# 10_Misc.net
KiCad netlist of a schematic drawn in Altium Designer
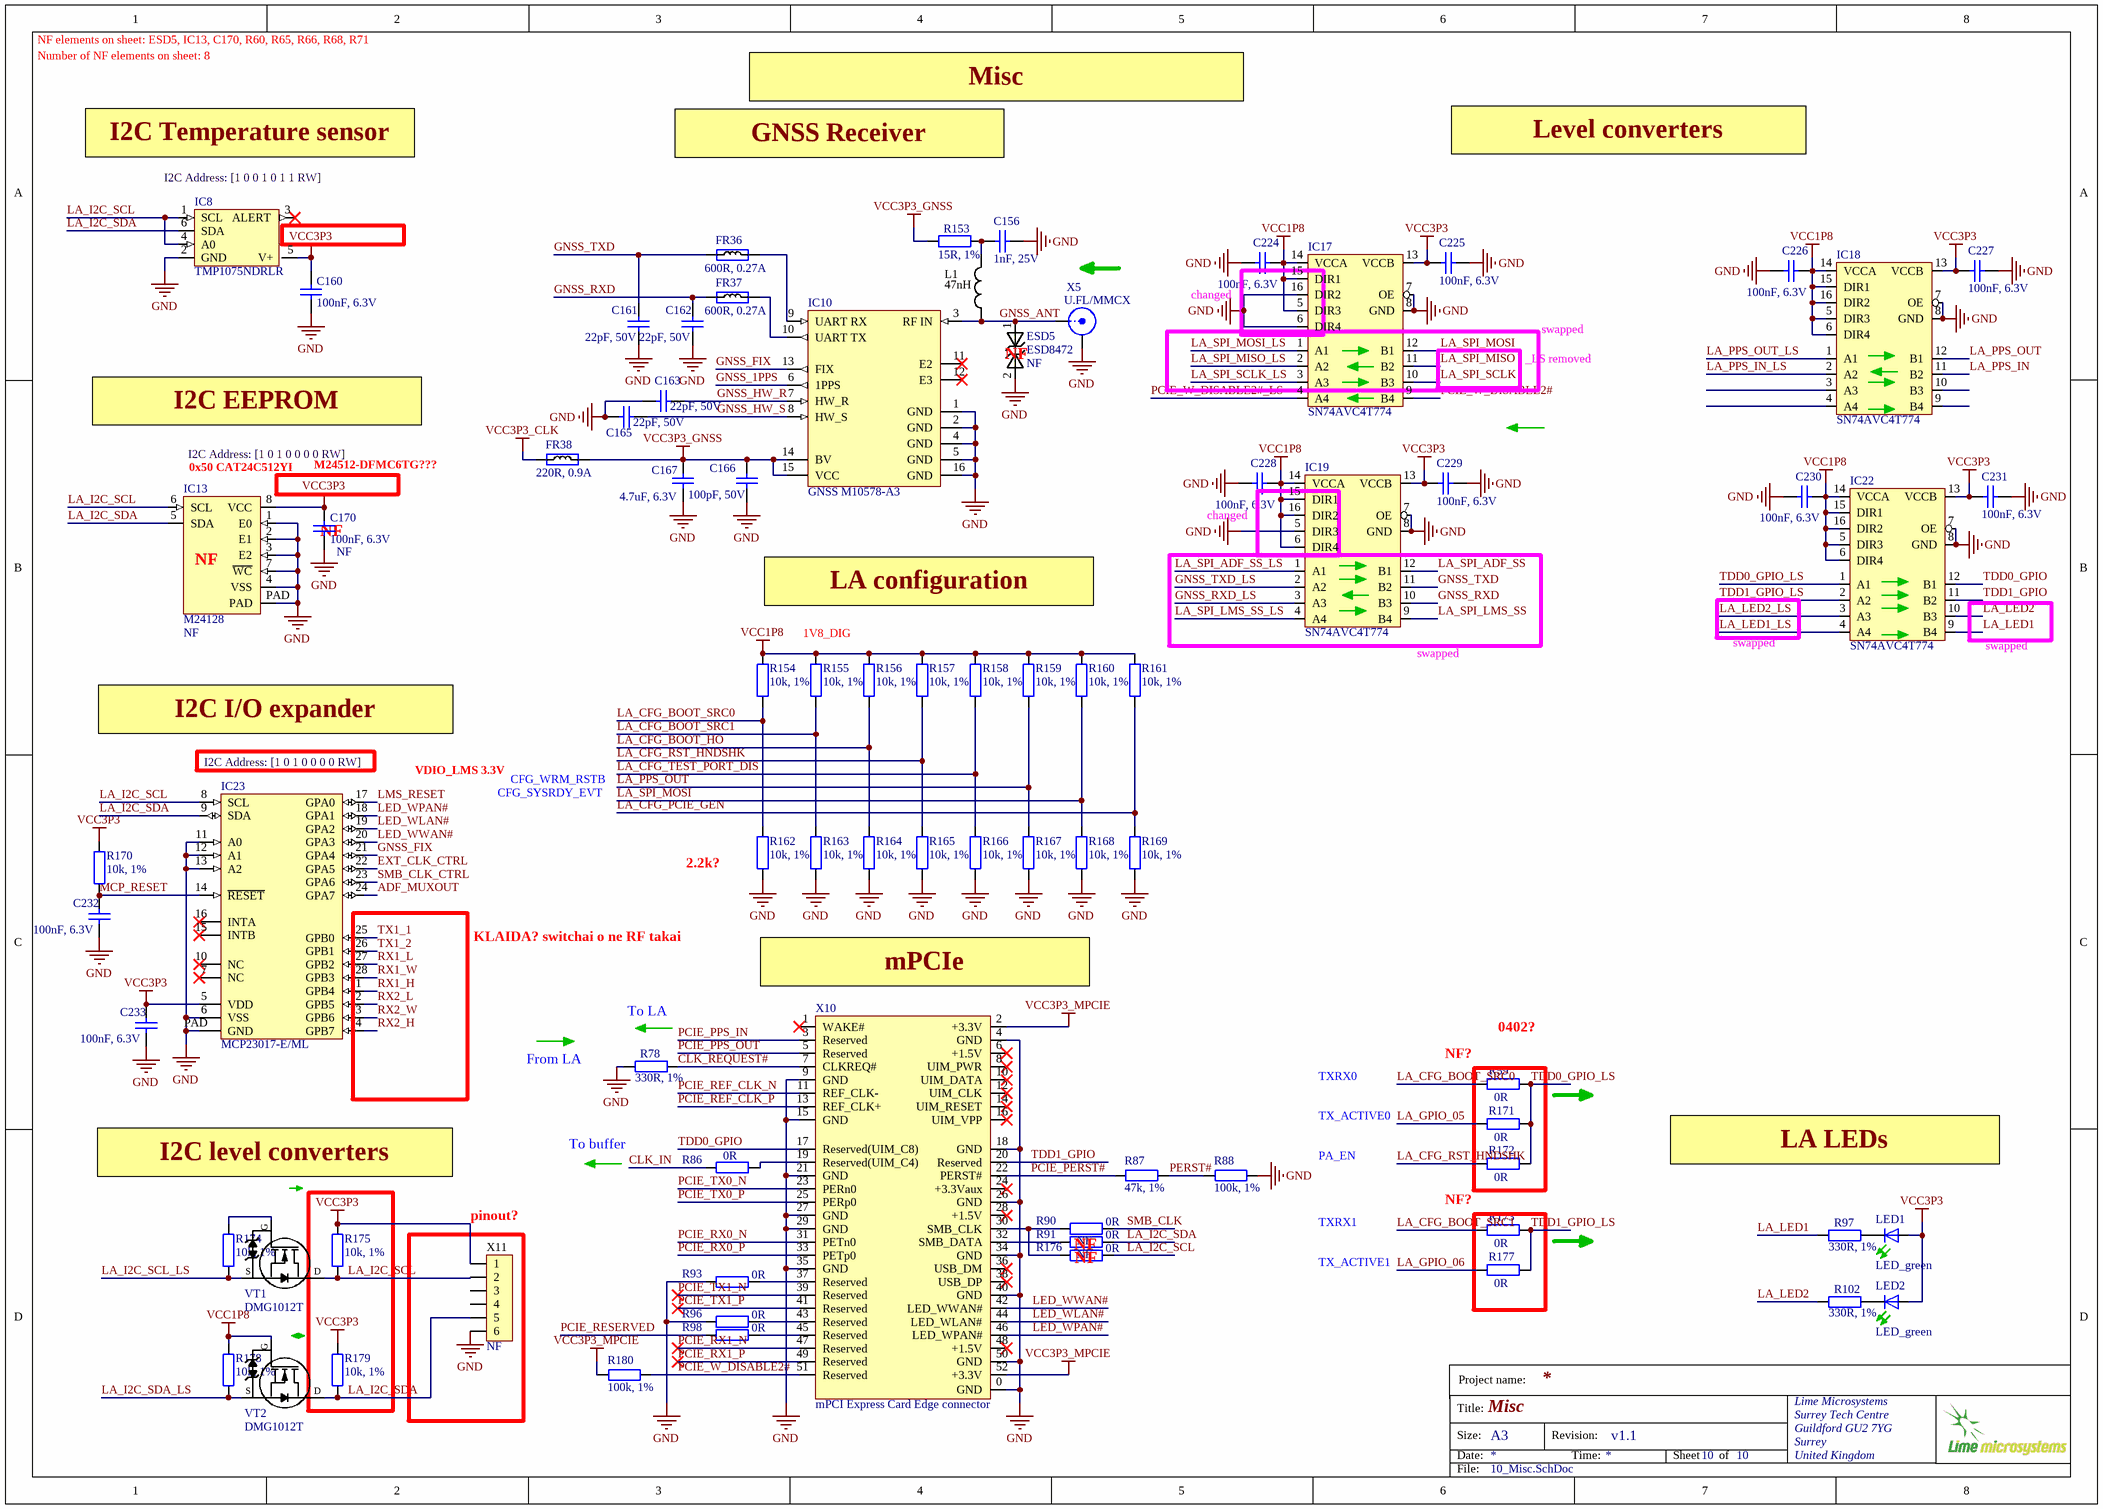
[diagram p0: 10_Misc.SchDoc]

(export (version "E")
  (design (tool "Eeschema 10.0.6"))
  (components
    (comp (ref "C156")
      (value "1nF, 25V")
      (footprint "CAP0201")
      (fields (field (name "TOLERANCE") "±10%") (field (name "MANUFACTURER") "TDK Corporation"))
      (libsource (lib "LimeMicroAltiumLib_schLib") (part "Cap_0402"))
    )
    (comp (ref "C160")
      (value "100nF, 6.3V")
      (footprint "CAP0201")
      (fields (field (name "MANUFACTURER") "Samsung") (field (name "TOLERANCE") "20%"))
      (libsource (lib "LimeMicroAltiumLib_schLib") (part "Cap_0402"))
    )
    (comp (ref "C161")
      (value "22pF, 50V")
      (footprint "CAP0201")
      (fields
        (field (name "MANUFACTURER") "Murata")
        (field (name "TOLERANCE") "5%")
        (field (name "VOLTAGE") "50V")
      )
      (libsource (lib "LimeMicroAltiumLib_schLib") (part "Cap_0402"))
    )
    (comp (ref "C162")
      (value "22pF, 50V")
      (footprint "CAP0201")
      (fields
        (field (name "MANUFACTURER") "Murata")
        (field (name "TOLERANCE") "5%")
        (field (name "VOLTAGE") "50V")
      )
      (libsource (lib "LimeMicroAltiumLib_schLib") (part "Cap_0402"))
    )
    (comp (ref "C163")
      (value "22pF, 50V")
      (footprint "CAP0201")
      (fields
        (field (name "MANUFACTURER") "Murata")
        (field (name "TOLERANCE") "5%")
        (field (name "VOLTAGE") "50V")
      )
      (libsource (lib "LimeMicroAltiumLib_schLib") (part "Cap_0402"))
    )
    (comp (ref "C165")
      (value "22pF, 50V")
      (footprint "CAP0201")
      (fields
        (field (name "MANUFACTURER") "Murata")
        (field (name "TOLERANCE") "5%")
        (field (name "VOLTAGE") "50V")
      )
      (libsource (lib "LimeMicroAltiumLib_schLib") (part "Cap_0402"))
    )
    (comp (ref "C166")
      (value "100pF, 50V")
      (footprint "CAP0201")
      (fields
        (field (name "MANUFACTURER") "TDK")
        (field (name "TOLERANCE") "5%")
        (field (name "VOLTAGE") "50V")
      )
      (libsource (lib "LimeMicroAltiumLib_schLib") (part "Cap_0402"))
    )
    (comp (ref "C167")
      (value "4.7uF, 6.3V")
      (footprint "CAP0402")
      (fields
        (field (name "MANUFACTURER") "Murata Electronics North America")
        (field (name "TOLERANCE") "±20%")
      )
      (libsource (lib "LimeMicroAltiumLib_schLib") (part "Cap_0402"))
    )
    (comp (ref "C170")
      (value "100nF, 6.3V")
      (footprint "CAP0201")
      (fields
        (field (name "ASSEMBLY INFO") "NF")
        (field (name "MANUFACTURER") "Samsung")
        (field (name "TOLERANCE") "20%")
      )
      (libsource (lib "LimeMicroAltiumLib_schLib") (part "Cap_0402"))
    )
    (comp (ref "C224")
      (value "100nF, 6.3V")
      (footprint "CAP0201")
      (fields (field (name "MANUFACTURER") "Samsung") (field (name "TOLERANCE") "20%"))
      (libsource (lib "LimeMicroAltiumLib_schLib") (part "Cap_0402"))
    )
    (comp (ref "C225")
      (value "100nF, 6.3V")
      (footprint "CAP0201")
      (fields (field (name "MANUFACTURER") "Samsung") (field (name "TOLERANCE") "20%"))
      (libsource (lib "LimeMicroAltiumLib_schLib") (part "Cap_0402"))
    )
    (comp (ref "C226")
      (value "100nF, 6.3V")
      (footprint "CAP0201")
      (fields (field (name "MANUFACTURER") "Samsung") (field (name "TOLERANCE") "20%"))
      (libsource (lib "LimeMicroAltiumLib_schLib") (part "Cap_0402"))
    )
    (comp (ref "C227")
      (value "100nF, 6.3V")
      (footprint "CAP0201")
      (fields (field (name "MANUFACTURER") "Samsung") (field (name "TOLERANCE") "20%"))
      (libsource (lib "LimeMicroAltiumLib_schLib") (part "Cap_0402"))
    )
    (comp (ref "C228")
      (value "100nF, 6.3V")
      (footprint "CAP0201")
      (fields (field (name "MANUFACTURER") "Samsung") (field (name "TOLERANCE") "20%"))
      (libsource (lib "LimeMicroAltiumLib_schLib") (part "Cap_0402"))
    )
    (comp (ref "C229")
      (value "100nF, 6.3V")
      (footprint "CAP0201")
      (fields (field (name "MANUFACTURER") "Samsung") (field (name "TOLERANCE") "20%"))
      (libsource (lib "LimeMicroAltiumLib_schLib") (part "Cap_0402"))
    )
    (comp (ref "C230")
      (value "100nF, 6.3V")
      (footprint "CAP0201")
      (fields (field (name "MANUFACTURER") "Samsung") (field (name "TOLERANCE") "20%"))
      (libsource (lib "LimeMicroAltiumLib_schLib") (part "Cap_0402"))
    )
    (comp (ref "C231")
      (value "100nF, 6.3V")
      (footprint "CAP0201")
      (fields (field (name "MANUFACTURER") "Samsung") (field (name "TOLERANCE") "20%"))
      (libsource (lib "LimeMicroAltiumLib_schLib") (part "Cap_0402"))
    )
    (comp (ref "C232")
      (value "100nF, 6.3V")
      (footprint "CAP0201")
      (fields (field (name "MANUFACTURER") "Samsung") (field (name "TOLERANCE") "20%"))
      (libsource (lib "LimeMicroAltiumLib_schLib") (part "Cap_0402"))
    )
    (comp (ref "C233")
      (value "100nF, 6.3V")
      (footprint "CAP0201")
      (fields (field (name "MANUFACTURER") "Samsung") (field (name "TOLERANCE") "20%"))
      (libsource (lib "LimeMicroAltiumLib_schLib") (part "Cap_0402"))
    )
    (comp (ref "ESD5")
      (value "ESD8472")
      (footprint "ESD8472_X3DFN2")
      (fields (field (name "MANUFACTURER") "ON Semiconductor") (field (name "ASSEMBLY INFO") "NF"))
      (libsource (lib "LimeMicroAltiumLib_schLib") (part "ESD8472"))
    )
    (comp (ref "FR36")
      (value "600R, 0.27A")
      (footprint "RES0201")
      (fields (field (name "MANUFACTURER") "Taiyo Yuden"))
      (libsource (lib "LimeMicroAltiumLib_schLib") (part "Ferrite"))
    )
    (comp (ref "FR37")
      (value "600R, 0.27A")
      (footprint "RES0201")
      (fields (field (name "MANUFACTURER") "Taiyo Yuden"))
      (libsource (lib "LimeMicroAltiumLib_schLib") (part "Ferrite"))
    )
    (comp (ref "FR38")
      (value "220R, 0.9A")
      (footprint "RES0402")
      (fields (field (name "MANUFACTURER") "TDK Corporation"))
      (libsource (lib "LimeFPGAboard_schLib") (part "Ferrite"))
    )
    (comp (ref "IC8")
      (value "TMP1075NDRLR")
      (footprint "TMP1075NDRLR_temperature_sensor_SOT563")
      (fields (field (name "MANUFACTURER") "Texas Instruments"))
      (libsource (lib "LimeMicroAltiumLib_schLib_r04") (part "TMP1075NDRLR_temperature_sensor"))
    )
    (comp (ref "IC10")
      (value "GNSS M10578-A3")
      (footprint "M10578-A3_v2")
      (fields (field (name "MANUFACTURER") "Antenova"))
      (libsource (lib "LimeMicroAltiumLib_schLib_r04") (part "M10578-A3_GPS_GNSS"))
    )
    (comp (ref "IC13")
      (value "M24128")
      (footprint "M24128-DFMC6TG")
      (fields (field (name "MANUFACTURER") "STMicroelectronics") (field (name "ASSEMBLY INFO") "NF"))
      (libsource (lib "LimeMicroAltiumLib_schLib") (part "M24128-DFMC6TG"))
    )
    (comp (ref "IC17")
      (value "SN74AVC4T774")
      (footprint "SN74AVC4T774")
      (fields (field (name "MANUFACTURER") "Texas Instruments"))
      (libsource (lib "LimeMicroAltiumLib") (part "SN74AVC4T774"))
    )
    (comp (ref "IC18")
      (value "SN74AVC4T774")
      (footprint "SN74AVC4T774")
      (fields (field (name "MANUFACTURER") "Texas Instruments"))
      (libsource (lib "LimeMicroAltiumLib") (part "SN74AVC4T774"))
    )
    (comp (ref "IC19")
      (value "SN74AVC4T774")
      (footprint "SN74AVC4T774")
      (fields (field (name "MANUFACTURER") "Texas Instruments"))
      (libsource (lib "LimeMicroAltiumLib") (part "SN74AVC4T774"))
    )
    (comp (ref "IC22")
      (value "SN74AVC4T774")
      (footprint "SN74AVC4T774")
      (fields (field (name "MANUFACTURER") "Texas Instruments"))
      (libsource (lib "LimeMicroAltiumLib") (part "SN74AVC4T774"))
    )
    (comp (ref "IC23")
      (value "MCP23017-E/ML")
      (footprint "MCP23017-E/ML_QFN28")
      (fields (field (name "MANUFACTURER") "Microchip"))
      (libsource (lib "LimeMicroAltiumLib") (part "MCP23017-E/ML_I2C_expander"))
    )
    (comp (ref "L1")
      (value "47nH")
      (footprint "RES0402")
      (fields
        (field (name "MANUFACTURER") "COILCRAFT")
        (field (name "MANUFACTURER PART NUMBER") "0402HP-47NXJLU")
      )
      (libsource (lib "LimeMicroAltiumLib_schLib") (part "Inductor_0603"))
    )
    (comp (ref "LED1")
      (value "LED_green")
      (footprint "LED0201")
      (fields (field (name "MANUFACTURER") "Kingbright"))
      (libsource (lib "LimeFPGAboard_schLib") (part "LED_green"))
    )
    (comp (ref "LED2")
      (value "LED_green")
      (footprint "LED0201")
      (fields (field (name "MANUFACTURER") "Kingbright"))
      (libsource (lib "LimeFPGAboard_schLib") (part "LED_green"))
    )
    (comp (ref "R59")
      (value "0R")
      (footprint "RES0201")
      (fields (field (name "MANUFACTURER") "Yageo") (field (name "TOLERANCE") "5%"))
      (libsource (lib "LimeFPGAboard_schLib") (part "Res_0402"))
    )
    (comp (ref "R78")
      (value "330R, 1%")
      (footprint "RES0201")
      (fields (field (name "MANUFACTURER") "Vishay Dale") (field (name "TOLERANCE") "1%"))
      (libsource (lib "LimeFPGAboard_schLib") (part "Res_0402"))
    )
    (comp (ref "R86")
      (value "0R")
      (footprint "RES0201")
      (fields (field (name "MANUFACTURER") "Yageo") (field (name "TOLERANCE") "5%"))
      (libsource (lib "LimeFPGAboard_schLib") (part "Res_0402"))
    )
    (comp (ref "R87")
      (value "47k, 1%")
      (footprint "RES0201")
      (fields (field (name "MANUFACTURER") "Yageo") (field (name "TOLERANCE") "1%"))
      (libsource (lib "LimeFPGAboard_schLib") (part "Res_0402"))
    )
    (comp (ref "R88")
      (value "100k, 1%")
      (footprint "RES0201")
      (fields (field (name "MANUFACTURER") "Yageo") (field (name "TOLERANCE") "1%"))
      (libsource (lib "LimeMicroAltiumLib_schLib") (part "Res_0402"))
    )
    (comp (ref "R90")
      (value "0R")
      (footprint "RES0201")
      (fields (field (name "MANUFACTURER") "Yageo") (field (name "TOLERANCE") "5%"))
      (libsource (lib "LimeFPGAboard_schLib") (part "Res_0402"))
    )
    (comp (ref "R91")
      (value "0R")
      (footprint "RES0201")
      (fields
        (field (name "ASSEMBLY INFO") "NF")
        (field (name "MANUFACTURER") "Yageo")
        (field (name "TOLERANCE") "5%")
      )
      (libsource (lib "LimeFPGAboard_schLib") (part "Res_0402"))
    )
    (comp (ref "R93")
      (value "0R")
      (footprint "RES0201")
      (fields (field (name "MANUFACTURER") "Yageo") (field (name "TOLERANCE") "5%"))
      (libsource (lib "LimeFPGAboard_schLib") (part "Res_0402"))
    )
    (comp (ref "R96")
      (value "0R")
      (footprint "RES0201")
      (fields (field (name "MANUFACTURER") "Yageo") (field (name "TOLERANCE") "5%"))
      (libsource (lib "LimeFPGAboard_schLib") (part "Res_0402"))
    )
    (comp (ref "R97")
      (value "330R, 1%")
      (footprint "RES0201")
      (fields (field (name "MANUFACTURER") "Vishay Dale") (field (name "TOLERANCE") "1%"))
      (libsource (lib "LimeFPGAboard_schLib") (part "Res_0402"))
    )
    (comp (ref "R98")
      (value "0R")
      (footprint "RES0201")
      (fields (field (name "MANUFACTURER") "Yageo") (field (name "TOLERANCE") "5%"))
      (libsource (lib "LimeFPGAboard_schLib") (part "Res_0402"))
    )
    (comp (ref "R102")
      (value "330R, 1%")
      (footprint "RES0201")
      (fields (field (name "MANUFACTURER") "Vishay Dale") (field (name "TOLERANCE") "1%"))
      (libsource (lib "LimeFPGAboard_schLib") (part "Res_0402"))
    )
    (comp (ref "R153")
      (value "15R, 1%")
      (footprint "RES0201")
      (fields (field (name "MANUFACTURER") "Yageo") (field (name "TOLERANCE") "1%"))
      (libsource (lib "LimeFPGAboard_schLib") (part "Res_0402"))
    )
    (comp (ref "R154")
      (value "10k, 1%")
      (footprint "RES0201")
      (fields (field (name "MANUFACTURER") "Yageo") (field (name "TOLERANCE") "1%"))
      (libsource (lib "LimeFPGAboard_schLib") (part "Res_0402"))
    )
    (comp (ref "R155")
      (value "10k, 1%")
      (footprint "RES0201")
      (fields (field (name "MANUFACTURER") "Yageo") (field (name "TOLERANCE") "1%"))
      (libsource (lib "LimeFPGAboard_schLib") (part "Res_0402"))
    )
    (comp (ref "R156")
      (value "10k, 1%")
      (footprint "RES0201")
      (fields (field (name "MANUFACTURER") "Yageo") (field (name "TOLERANCE") "1%"))
      (libsource (lib "LimeFPGAboard_schLib") (part "Res_0402"))
    )
    (comp (ref "R157")
      (value "10k, 1%")
      (footprint "RES0201")
      (fields (field (name "MANUFACTURER") "Yageo") (field (name "TOLERANCE") "1%"))
      (libsource (lib "LimeFPGAboard_schLib") (part "Res_0402"))
    )
    (comp (ref "R158")
      (value "10k, 1%")
      (footprint "RES0201")
      (fields (field (name "MANUFACTURER") "Yageo") (field (name "TOLERANCE") "1%"))
      (libsource (lib "LimeFPGAboard_schLib") (part "Res_0402"))
    )
    (comp (ref "R159")
      (value "10k, 1%")
      (footprint "RES0201")
      (fields (field (name "MANUFACTURER") "Yageo") (field (name "TOLERANCE") "1%"))
      (libsource (lib "LimeFPGAboard_schLib") (part "Res_0402"))
    )
    (comp (ref "R160")
      (value "10k, 1%")
      (footprint "RES0201")
      (fields (field (name "MANUFACTURER") "Yageo") (field (name "TOLERANCE") "1%"))
      (libsource (lib "LimeFPGAboard_schLib") (part "Res_0402"))
    )
    (comp (ref "R161")
      (value "10k, 1%")
      (footprint "RES0201")
      (fields (field (name "MANUFACTURER") "Yageo") (field (name "TOLERANCE") "1%"))
      (libsource (lib "LimeFPGAboard_schLib") (part "Res_0402"))
    )
    (comp (ref "R162")
      (value "10k, 1%")
      (footprint "RES0201")
      (fields (field (name "MANUFACTURER") "Yageo") (field (name "TOLERANCE") "1%"))
      (libsource (lib "LimeFPGAboard_schLib") (part "Res_0402"))
    )
    (comp (ref "R163")
      (value "10k, 1%")
      (footprint "RES0201")
      (fields (field (name "MANUFACTURER") "Yageo") (field (name "TOLERANCE") "1%"))
      (libsource (lib "LimeFPGAboard_schLib") (part "Res_0402"))
    )
    (comp (ref "R164")
      (value "10k, 1%")
      (footprint "RES0201")
      (fields (field (name "MANUFACTURER") "Yageo") (field (name "TOLERANCE") "1%"))
      (libsource (lib "LimeFPGAboard_schLib") (part "Res_0402"))
    )
    (comp (ref "R165")
      (value "10k, 1%")
      (footprint "RES0201")
      (fields (field (name "MANUFACTURER") "Yageo") (field (name "TOLERANCE") "1%"))
      (libsource (lib "LimeFPGAboard_schLib") (part "Res_0402"))
    )
    (comp (ref "R166")
      (value "10k, 1%")
      (footprint "RES0201")
      (fields (field (name "MANUFACTURER") "Yageo") (field (name "TOLERANCE") "1%"))
      (libsource (lib "LimeFPGAboard_schLib") (part "Res_0402"))
    )
    (comp (ref "R167")
      (value "10k, 1%")
      (footprint "RES0201")
      (fields (field (name "MANUFACTURER") "Yageo") (field (name "TOLERANCE") "1%"))
      (libsource (lib "LimeFPGAboard_schLib") (part "Res_0402"))
    )
    (comp (ref "R168")
      (value "10k, 1%")
      (footprint "RES0201")
      (fields (field (name "MANUFACTURER") "Yageo") (field (name "TOLERANCE") "1%"))
      (libsource (lib "LimeFPGAboard_schLib") (part "Res_0402"))
    )
    (comp (ref "R169")
      (value "10k, 1%")
      (footprint "RES0201")
      (fields (field (name "MANUFACTURER") "Yageo") (field (name "TOLERANCE") "1%"))
      (libsource (lib "LimeFPGAboard_schLib") (part "Res_0402"))
    )
    (comp (ref "R170")
      (value "10k, 1%")
      (footprint "RES0201")
      (fields (field (name "MANUFACTURER") "Yageo") (field (name "TOLERANCE") "1%"))
      (libsource (lib "LimeFPGAboard_schLib") (part "Res_0402"))
    )
    (comp (ref "R171")
      (value "0R")
      (footprint "RES0201")
      (fields (field (name "MANUFACTURER") "Yageo") (field (name "TOLERANCE") "5%"))
      (libsource (lib "LimeFPGAboard_schLib") (part "Res_0402"))
    )
    (comp (ref "R172")
      (value "0R")
      (footprint "RES0201")
      (fields (field (name "MANUFACTURER") "Yageo") (field (name "TOLERANCE") "5%"))
      (libsource (lib "LimeFPGAboard_schLib") (part "Res_0402"))
    )
    (comp (ref "R173")
      (value "0R")
      (footprint "RES0201")
      (fields (field (name "MANUFACTURER") "Yageo") (field (name "TOLERANCE") "5%"))
      (libsource (lib "LimeFPGAboard_schLib") (part "Res_0402"))
    )
    (comp (ref "R174")
      (value "10k, 1%")
      (footprint "RES0201")
      (fields (field (name "MANUFACTURER") "Yageo") (field (name "TOLERANCE") "1%"))
      (libsource (lib "LimeFPGAboard_schLib") (part "Res_0402"))
    )
    (comp (ref "R175")
      (value "10k, 1%")
      (footprint "RES0201")
      (fields (field (name "MANUFACTURER") "Yageo") (field (name "TOLERANCE") "1%"))
      (libsource (lib "LimeFPGAboard_schLib") (part "Res_0402"))
    )
    (comp (ref "R176")
      (value "0R")
      (footprint "RES0201")
      (fields
        (field (name "ASSEMBLY INFO") "NF")
        (field (name "MANUFACTURER") "Yageo")
        (field (name "TOLERANCE") "5%")
      )
      (libsource (lib "LimeFPGAboard_schLib") (part "Res_0402"))
    )
    (comp (ref "R177")
      (value "0R")
      (footprint "RES0201")
      (fields (field (name "MANUFACTURER") "Yageo") (field (name "TOLERANCE") "5%"))
      (libsource (lib "LimeFPGAboard_schLib") (part "Res_0402"))
    )
    (comp (ref "R178")
      (value "10k, 1%")
      (footprint "RES0201")
      (fields (field (name "MANUFACTURER") "Yageo") (field (name "TOLERANCE") "1%"))
      (libsource (lib "LimeFPGAboard_schLib") (part "Res_0402"))
    )
    (comp (ref "R179")
      (value "10k, 1%")
      (footprint "RES0201")
      (fields (field (name "MANUFACTURER") "Yageo") (field (name "TOLERANCE") "1%"))
      (libsource (lib "LimeFPGAboard_schLib") (part "Res_0402"))
    )
    (comp (ref "R180")
      (value "100k, 1%")
      (footprint "RES0201")
      (fields (field (name "MANUFACTURER") "Yageo") (field (name "TOLERANCE") "1%"))
      (libsource (lib "LimeMicroAltiumLib_schLib") (part "Res_0402"))
    )
    (comp (ref "VT1")
      (value "DMG1012T")
      (footprint "SOT523")
      (fields (field (name "MANUFACTURER") "Diodes Incorporated"))
      (libsource (lib "LimeMicroAltiumLib_schLib_r01") (part "DMG1012T"))
    )
    (comp (ref "VT2")
      (value "DMG1012T")
      (footprint "SOT523")
      (fields (field (name "MANUFACTURER") "Diodes Incorporated"))
      (libsource (lib "LimeMicroAltiumLib_schLib_r01") (part "DMG1012T"))
    )
    (comp (ref "X5")
      (value "U.FL/MMCX")
      (footprint "MMCX_UFL_conn_u_v2")
      (description "CONN UMC RCPT STR 50 OHM SMD")
      (fields (field (name "MANUFACTURER") "Molex, LLC"))
      (libsource (lib "LimeMicroAltiumLib_schLib") (part "RF_IF_connector"))
    )
    (comp (ref "X10")
      (value "mPCI Express Card Edge connector")
      (footprint "PCIe_MiniCard")
      (description "PCIe MiniCard full or half size")
      (libsource (lib "LimeMicroAltiumLib_schLib_r04") (part "PCIe_MiniCard_fingers"))
    )
    (comp (ref "X11")
      (value "Molex 0788641001")
      (footprint "Molex_0788641001_spring_contacts")
      (description "Header, 6-pin")
      (fields (field (name "MANUFACTURER") "Molex") (field (name "ASSEMBLY INFO") "NF"))
      (libsource (lib "LimeMicroAltiumLib_schLib_r04") (part "Molex_0788641001_spring_contacts"))
    )
  )
  (nets
    (net (code "1") (name "/ADF_MUXOUT") (class "Default")
      (node (ref "IC23") (pin "24") (pinfunction "GPA7_24") (pintype "bidirectional"))
    )
    (net (code "2") (name "/CLK_IN") (class "Default")
      (node (ref "R86") (pin "1") (pinfunction "1_1") (pintype "passive"))
    )
    (net (code "3") (name "/CLK_REQUEST#") (class "Default")
      (node (ref "R78") (pin "1") (pinfunction "1_1") (pintype "passive"))
      (node (ref "X10") (pin "7") (pinfunction "CLKREQ#_7") (pintype "passive"))
    )
    (net (code "4") (name "/EXT_CLK_CTRL") (class "Default")
      (node (ref "IC23") (pin "22") (pinfunction "GPA5_22") (pintype "bidirectional"))
    )
    (net (code "5") (name "/GNSS_1PPS") (class "Default")
      (node (ref "IC10") (pin "6") (pinfunction "1PPS_6") (pintype "output"))
    )
    (net (code "6") (name "/GNSS_ANT") (class "Default")
      (node (ref "ESD5") (pin "1") (pinfunction "1_1") (pintype "passive"))
      (node (ref "IC10") (pin "3") (pinfunction "RF_IN_3") (pintype "input"))
      (node (ref "L1") (pin "1") (pinfunction "1_1") (pintype "passive"))
      (node (ref "X5") (pin "1") (pinfunction "X_1") (pintype "passive"))
    )
    (net (code "7") (name "/GNSS_FIX") (class "Default")
      (node (ref "IC10") (pin "13") (pinfunction "FIX_13") (pintype "output"))
      (node (ref "IC23") (pin "21") (pinfunction "GPA4_21") (pintype "bidirectional"))
    )
    (net (code "8") (name "/GNSS_HW_R") (class "Default")
      (node (ref "C163") (pin "1") (pinfunction "1_1") (pintype "passive"))
      (node (ref "IC10") (pin "7") (pinfunction "HW_R_7") (pintype "input"))
    )
    (net (code "9") (name "/GNSS_HW_S") (class "Default")
      (node (ref "C165") (pin "1") (pinfunction "1_1") (pintype "passive"))
      (node (ref "IC10") (pin "8") (pinfunction "HW_S_8") (pintype "input"))
    )
    (net (code "10") (name "/GNSS_RXD") (class "Default")
      (node (ref "C162") (pin "1") (pinfunction "1_1") (pintype "passive"))
      (node (ref "FR37") (pin "1") (pinfunction "1_1") (pintype "passive"))
      (node (ref "IC19") (pin "10") (pinfunction "B3_10") (pintype "passive"))
    )
    (net (code "11") (name "/GNSS_RXD_LS") (class "Default")
      (node (ref "IC19") (pin "3") (pinfunction "A3_3") (pintype "passive"))
    )
    (net (code "12") (name "/GNSS_TXD") (class "Default")
      (node (ref "C161") (pin "1") (pinfunction "1_1") (pintype "passive"))
      (node (ref "FR36") (pin "1") (pinfunction "1_1") (pintype "passive"))
      (node (ref "IC19") (pin "11") (pinfunction "B2_11") (pintype "passive"))
    )
    (net (code "13") (name "/GNSS_TXD_LS") (class "Default")
      (node (ref "IC19") (pin "2") (pinfunction "A2_2") (pintype "passive"))
    )
    (net (code "14") (name "/LA_CFG_BOOT_HO") (class "Default")
      (node (ref "R156") (pin "2") (pinfunction "2_2") (pintype "passive"))
      (node (ref "R164") (pin "1") (pinfunction "1_1") (pintype "passive"))
    )
    (net (code "15") (name "/LA_CFG_BOOT_SRC0") (class "Default")
      (node (ref "R154") (pin "2") (pinfunction "2_2") (pintype "passive"))
      (node (ref "R162") (pin "1") (pinfunction "1_1") (pintype "passive"))
      (node (ref "R59") (pin "1") (pinfunction "1_1") (pintype "passive"))
    )
    (net (code "16") (name "/LA_CFG_BOOT_SRC1") (class "Default")
      (node (ref "R155") (pin "2") (pinfunction "2_2") (pintype "passive"))
      (node (ref "R163") (pin "1") (pinfunction "1_1") (pintype "passive"))
      (node (ref "R173") (pin "1") (pinfunction "1_1") (pintype "passive"))
    )
    (net (code "17") (name "/LA_CFG_PCIE_GEN") (class "Default")
      (node (ref "R161") (pin "2") (pinfunction "2_2") (pintype "passive"))
      (node (ref "R169") (pin "1") (pinfunction "1_1") (pintype "passive"))
    )
    (net (code "18") (name "/LA_CFG_RST_HNDSHK") (class "Default")
      (node (ref "R157") (pin "2") (pinfunction "2_2") (pintype "passive"))
      (node (ref "R165") (pin "1") (pinfunction "1_1") (pintype "passive"))
      (node (ref "R172") (pin "1") (pinfunction "1_1") (pintype "passive"))
    )
    (net (code "19") (name "/LA_CFG_TEST_PORT_DIS") (class "Default")
      (node (ref "R158") (pin "2") (pinfunction "2_2") (pintype "passive"))
      (node (ref "R166") (pin "1") (pinfunction "1_1") (pintype "passive"))
    )
    (net (code "20") (name "/LA_GPIO_05") (class "Default")
      (node (ref "R171") (pin "1") (pinfunction "1_1") (pintype "passive"))
    )
    (net (code "21") (name "/LA_GPIO_06") (class "Default")
      (node (ref "R177") (pin "1") (pinfunction "1_1") (pintype "passive"))
    )
    (net (code "22") (name "/LA_I2C_SCL") (class "Default")
      (node (ref "IC13") (pin "6") (pinfunction "SCL_6") (pintype "input"))
      (node (ref "IC23") (pin "8") (pinfunction "SCL_8") (pintype "input"))
      (node (ref "IC8") (pin "1") (pinfunction "SCL_1") (pintype "input"))
      (node (ref "IC8") (pin "4") (pinfunction "A0_4") (pintype "input"))
      (node (ref "R175") (pin "2") (pinfunction "2_2") (pintype "passive"))
      (node (ref "R176") (pin "2") (pinfunction "2_2") (pintype "passive"))
      (node (ref "VT1") (pin "D") (pinfunction "D_D") (pintype "passive"))
      (node (ref "X11") (pin "2") (pinfunction "2_2") (pintype "passive"))
    )
    (net (code "23") (name "/LA_I2C_SCL_LS") (class "Default")
      (node (ref "R174") (pin "2") (pinfunction "2_2") (pintype "passive"))
      (node (ref "VT1") (pin "S") (pinfunction "S_S") (pintype "passive"))
    )
    (net (code "24") (name "/LA_I2C_SDA") (class "Default")
      (node (ref "IC13") (pin "5") (pinfunction "SDA_5") (pintype "bidirectional"))
      (node (ref "IC23") (pin "9") (pinfunction "SDA_9") (pintype "bidirectional"))
      (node (ref "IC8") (pin "6") (pinfunction "SDA_6") (pintype "bidirectional"))
      (node (ref "R179") (pin "2") (pinfunction "2_2") (pintype "passive"))
      (node (ref "R91") (pin "2") (pinfunction "2_2") (pintype "passive"))
      (node (ref "VT2") (pin "D") (pinfunction "D_D") (pintype "passive"))
      (node (ref "X11") (pin "5") (pinfunction "5_5") (pintype "passive"))
    )
    (net (code "25") (name "/LA_I2C_SDA_LS") (class "Default")
      (node (ref "R178") (pin "2") (pinfunction "2_2") (pintype "passive"))
      (node (ref "VT2") (pin "S") (pinfunction "S_S") (pintype "passive"))
    )
    (net (code "26") (name "/LA_LED1") (class "Default")
      (node (ref "IC22") (pin "9") (pinfunction "B4_9") (pintype "passive"))
      (node (ref "R97") (pin "2") (pinfunction "2_2") (pintype "passive"))
    )
    (net (code "27") (name "/LA_LED1_LS") (class "Default")
      (node (ref "IC22") (pin "4") (pinfunction "A4_4") (pintype "passive"))
    )
    (net (code "28") (name "/LA_LED2") (class "Default")
      (node (ref "IC22") (pin "10") (pinfunction "B3_10") (pintype "passive"))
      (node (ref "R102") (pin "2") (pinfunction "2_2") (pintype "passive"))
    )
    (net (code "29") (name "/LA_LED2_LS") (class "Default")
      (node (ref "IC22") (pin "3") (pinfunction "A3_3") (pintype "passive"))
    )
    (net (code "30") (name "/LA_PPS_IN") (class "Default")
      (node (ref "IC18") (pin "11") (pinfunction "B2_11") (pintype "passive"))
    )
    (net (code "31") (name "/LA_PPS_IN_LS") (class "Default")
      (node (ref "IC18") (pin "2") (pinfunction "A2_2") (pintype "passive"))
    )
    (net (code "32") (name "/LA_PPS_OUT") (class "Default")
      (node (ref "IC18") (pin "12") (pinfunction "B1_12") (pintype "passive"))
      (node (ref "R159") (pin "2") (pinfunction "2_2") (pintype "passive"))
      (node (ref "R167") (pin "1") (pinfunction "1_1") (pintype "passive"))
    )
    (net (code "33") (name "/LA_PPS_OUT_LS") (class "Default")
      (node (ref "IC18") (pin "1") (pinfunction "A1_1") (pintype "passive"))
    )
    (net (code "34") (name "/LA_SPI_ADF_SS") (class "Default")
      (node (ref "IC19") (pin "12") (pinfunction "B1_12") (pintype "passive"))
    )
    (net (code "35") (name "/LA_SPI_ADF_SS_LS") (class "Default")
      (node (ref "IC19") (pin "1") (pinfunction "A1_1") (pintype "passive"))
    )
    (net (code "36") (name "/LA_SPI_LMS_SS") (class "Default")
      (node (ref "IC19") (pin "9") (pinfunction "B4_9") (pintype "passive"))
    )
    (net (code "37") (name "/LA_SPI_LMS_SS_LS") (class "Default")
      (node (ref "IC19") (pin "4") (pinfunction "A4_4") (pintype "passive"))
    )
    (net (code "38") (name "/LA_SPI_MISO") (class "Default")
      (node (ref "IC17") (pin "11") (pinfunction "B2_11") (pintype "passive"))
    )
    (net (code "39") (name "/LA_SPI_MISO_LS") (class "Default")
      (node (ref "IC17") (pin "2") (pinfunction "A2_2") (pintype "passive"))
    )
    (net (code "40") (name "/LA_SPI_MOSI") (class "Default")
      (node (ref "IC17") (pin "12") (pinfunction "B1_12") (pintype "passive"))
      (node (ref "R160") (pin "2") (pinfunction "2_2") (pintype "passive"))
      (node (ref "R168") (pin "1") (pinfunction "1_1") (pintype "passive"))
    )
    (net (code "41") (name "/LA_SPI_MOSI_LS") (class "Default")
      (node (ref "IC17") (pin "1") (pinfunction "A1_1") (pintype "passive"))
    )
    (net (code "42") (name "/LA_SPI_SCLK") (class "Default")
      (node (ref "IC17") (pin "10") (pinfunction "B3_10") (pintype "passive"))
    )
    (net (code "43") (name "/LA_SPI_SCLK_LS") (class "Default")
      (node (ref "IC17") (pin "3") (pinfunction "A3_3") (pintype "passive"))
    )
    (net (code "44") (name "/LED_WLAN#") (class "Default")
      (node (ref "IC23") (pin "19") (pinfunction "GPA2_19") (pintype "bidirectional"))
      (node (ref "X10") (pin "44") (pinfunction "LED_WLAN#_44") (pintype "passive"))
    )
    (net (code "45") (name "/LED_WPAN#") (class "Default")
      (node (ref "IC23") (pin "18") (pinfunction "GPA1_18") (pintype "bidirectional"))
      (node (ref "X10") (pin "46") (pinfunction "LED_WPAN#_46") (pintype "passive"))
    )
    (net (code "46") (name "/LED_WWAN#") (class "Default")
      (node (ref "IC23") (pin "20") (pinfunction "GPA3_20") (pintype "bidirectional"))
      (node (ref "X10") (pin "42") (pinfunction "LED_WWAN#_42") (pintype "passive"))
    )
    (net (code "47") (name "/LMS_RESET") (class "Default")
      (node (ref "IC23") (pin "17") (pinfunction "GPA0_17") (pintype "bidirectional"))
    )
    (net (code "48") (name "/MCP_RESET") (class "Default")
      (node (ref "C232") (pin "1") (pinfunction "1_1") (pintype "passive"))
      (node (ref "IC23") (pin "14") (pinfunction "~{RESET}_14") (pintype "input"))
      (node (ref "R170") (pin "2") (pinfunction "2_2") (pintype "passive"))
    )
    (net (code "49") (name "/PCIE_PERST#") (class "Default")
      (node (ref "R87") (pin "1") (pinfunction "1_1") (pintype "passive"))
      (node (ref "X10") (pin "22") (pinfunction "PERST#_22") (pintype "passive"))
    )
    (net (code "50") (name "/PCIE_PPS_IN") (class "Default")
      (node (ref "X10") (pin "3") (pinfunction "Reserved_3") (pintype "passive"))
    )
    (net (code "51") (name "/PCIE_PPS_OUT") (class "Default")
      (node (ref "X10") (pin "5") (pinfunction "Reserved_5") (pintype "passive"))
    )
    (net (code "52") (name "/PCIE_REF_CLK_N") (class "Default")
      (node (ref "X10") (pin "11") (pinfunction "REF_CLK-_11") (pintype "passive"))
    )
    (net (code "53") (name "/PCIE_REF_CLK_P") (class "Default")
      (node (ref "X10") (pin "13") (pinfunction "REF_CLK+_13") (pintype "passive"))
    )
    (net (code "54") (name "/PCIE_RESERVED") (class "Default")
      (node (ref "R98") (pin "1") (pinfunction "1_1") (pintype "passive"))
    )
    (net (code "55") (name "/PCIE_RX0_N") (class "Default")
      (node (ref "X10") (pin "31") (pinfunction "PETn0_31") (pintype "passive"))
    )
    (net (code "56") (name "/PCIE_RX0_P") (class "Default")
      (node (ref "X10") (pin "33") (pinfunction "PETp0_33") (pintype "passive"))
    )
    (net (code "57") (name "/PCIE_RX1_N") (class "Default")
      (node (ref "X10") (pin "47") (pinfunction "Reserved_47") (pintype "passive+no_connect"))
    )
    (net (code "58") (name "/PCIE_RX1_P") (class "Default")
      (node (ref "X10") (pin "49") (pinfunction "Reserved_49") (pintype "passive+no_connect"))
    )
    (net (code "59") (name "/PCIE_TX0_N") (class "Default")
      (node (ref "X10") (pin "23") (pinfunction "PERn0_23") (pintype "passive"))
    )
    (net (code "60") (name "/PCIE_TX0_P") (class "Default")
      (node (ref "X10") (pin "25") (pinfunction "PERp0_25") (pintype "passive"))
    )
    (net (code "61") (name "/PCIE_TX1_N") (class "Default")
      (node (ref "X10") (pin "39") (pinfunction "Reserved_39") (pintype "passive+no_connect"))
    )
    (net (code "62") (name "/PCIE_TX1_P") (class "Default")
      (node (ref "X10") (pin "41") (pinfunction "Reserved_41") (pintype "passive+no_connect"))
    )
    (net (code "63") (name "/PCIE_W_DISABLE2#") (class "Default")
      (node (ref "IC17") (pin "9") (pinfunction "B4_9") (pintype "passive"))
      (node (ref "R180") (pin "1") (pinfunction "1_1") (pintype "passive"))
      (node (ref "X10") (pin "51") (pinfunction "Reserved_51") (pintype "passive"))
    )
    (net (code "64") (name "/PCIE_W_DISABLE2#_LS") (class "Default")
      (node (ref "IC17") (pin "4") (pinfunction "A4_4") (pintype "passive"))
    )
    (net (code "65") (name "/PERST#") (class "Default")
      (node (ref "R87") (pin "2") (pinfunction "2_2") (pintype "passive"))
      (node (ref "R88") (pin "2") (pinfunction "2_2") (pintype "passive"))
    )
    (net (code "66") (name "/RX1_H") (class "Default")
      (node (ref "IC23") (pin "1") (pinfunction "GPB4_1") (pintype "bidirectional"))
    )
    (net (code "67") (name "/RX1_L") (class "Default")
      (node (ref "IC23") (pin "27") (pinfunction "GPB2_27") (pintype "bidirectional"))
    )
    (net (code "68") (name "/RX1_W") (class "Default")
      (node (ref "IC23") (pin "28") (pinfunction "GPB3_28") (pintype "bidirectional"))
    )
    (net (code "69") (name "/RX2_H") (class "Default")
      (node (ref "IC23") (pin "4") (pinfunction "GPB7_4") (pintype "bidirectional"))
    )
    (net (code "70") (name "/RX2_L") (class "Default")
      (node (ref "IC23") (pin "2") (pinfunction "GPB5_2") (pintype "bidirectional"))
    )
    (net (code "71") (name "/RX2_W") (class "Default")
      (node (ref "IC23") (pin "3") (pinfunction "GPB6_3") (pintype "bidirectional"))
    )
    (net (code "72") (name "/SMB_CLK") (class "Default")
      (node (ref "R90") (pin "2") (pinfunction "2_2") (pintype "passive"))
    )
    (net (code "73") (name "/SMB_CLK_CTRL") (class "Default")
      (node (ref "IC23") (pin "23") (pinfunction "GPA6_23") (pintype "bidirectional"))
    )
    (net (code "74") (name "/TDD0_GPIO") (class "Default")
      (node (ref "IC22") (pin "12") (pinfunction "B1_12") (pintype "passive"))
      (node (ref "X10") (pin "17") (pinfunction "Reserved(UIM_C8)_17") (pintype "passive"))
    )
    (net (code "75") (name "/TDD0_GPIO_LS") (class "Default")
      (node (ref "IC22") (pin "1") (pinfunction "A1_1") (pintype "passive"))
      (node (ref "R171") (pin "2") (pinfunction "2_2") (pintype "passive"))
      (node (ref "R172") (pin "2") (pinfunction "2_2") (pintype "passive"))
      (node (ref "R59") (pin "2") (pinfunction "2_2") (pintype "passive"))
    )
    (net (code "76") (name "/TDD1_GPIO") (class "Default")
      (node (ref "IC22") (pin "11") (pinfunction "B2_11") (pintype "passive"))
      (node (ref "X10") (pin "20") (pinfunction "Reserved_20") (pintype "passive"))
    )
    (net (code "77") (name "/TDD1_GPIO_LS") (class "Default")
      (node (ref "IC22") (pin "2") (pinfunction "A2_2") (pintype "passive"))
      (node (ref "R173") (pin "2") (pinfunction "2_2") (pintype "passive"))
      (node (ref "R177") (pin "2") (pinfunction "2_2") (pintype "passive"))
    )
    (net (code "78") (name "/TX1_1") (class "Default")
      (node (ref "IC23") (pin "25") (pinfunction "GPB0_25") (pintype "bidirectional"))
    )
    (net (code "79") (name "/TX1_2") (class "Default")
      (node (ref "IC23") (pin "26") (pinfunction "GPB1_26") (pintype "bidirectional"))
    )
    (net (code "80") (name "GND") (class "Default")
      (node (ref "C156") (pin "2") (pinfunction "2_2") (pintype "passive"))
      (node (ref "C160") (pin "2") (pinfunction "2_2") (pintype "passive"))
      (node (ref "C161") (pin "2") (pinfunction "2_2") (pintype "passive"))
      (node (ref "C162") (pin "2") (pinfunction "2_2") (pintype "passive"))
      (node (ref "C163") (pin "2") (pinfunction "2_2") (pintype "passive"))
      (node (ref "C165") (pin "2") (pinfunction "2_2") (pintype "passive"))
      (node (ref "C166") (pin "1") (pinfunction "1_1") (pintype "passive"))
      (node (ref "C167") (pin "1") (pinfunction "1_1") (pintype "passive"))
      (node (ref "C170") (pin "2") (pinfunction "2_2") (pintype "passive"))
      (node (ref "C224") (pin "1") (pinfunction "1_1") (pintype "passive"))
      (node (ref "C225") (pin "2") (pinfunction "2_2") (pintype "passive"))
      (node (ref "C226") (pin "1") (pinfunction "1_1") (pintype "passive"))
      (node (ref "C227") (pin "2") (pinfunction "2_2") (pintype "passive"))
      (node (ref "C228") (pin "1") (pinfunction "1_1") (pintype "passive"))
      (node (ref "C229") (pin "2") (pinfunction "2_2") (pintype "passive"))
      (node (ref "C230") (pin "1") (pinfunction "1_1") (pintype "passive"))
      (node (ref "C231") (pin "2") (pinfunction "2_2") (pintype "passive"))
      (node (ref "C232") (pin "2") (pinfunction "2_2") (pintype "passive"))
      (node (ref "C233") (pin "2") (pinfunction "2_2") (pintype "passive"))
      (node (ref "ESD5") (pin "2") (pinfunction "2_2") (pintype "passive"))
      (node (ref "IC10") (pin "1") (pinfunction "GND_1") (pintype "passive"))
      (node (ref "IC10") (pin "16") (pinfunction "GND_16") (pintype "passive"))
      (node (ref "IC10") (pin "2") (pinfunction "GND_2") (pintype "passive"))
      (node (ref "IC10") (pin "4") (pinfunction "GND_4") (pintype "passive"))
      (node (ref "IC10") (pin "5") (pinfunction "GND_5") (pintype "passive"))
      (node (ref "IC13") (pin "1") (pinfunction "E0_1") (pintype "input"))
      (node (ref "IC13") (pin "2") (pinfunction "E1_2") (pintype "input"))
      (node (ref "IC13") (pin "3") (pinfunction "E2_3") (pintype "input"))
      (node (ref "IC13") (pin "4") (pinfunction "VSS_4") (pintype "power_in"))
      (node (ref "IC13") (pin "7") (pinfunction "~{WC}_7") (pintype "input"))
      (node (ref "IC13") (pin "PAD") (pinfunction "PAD_PAD") (pintype "power_in"))
      (node (ref "IC17") (pin "16") (pinfunction "DIR2_16") (pintype "passive"))
      (node (ref "IC17") (pin "6") (pinfunction "DIR4_6") (pintype "passive"))
      (node (ref "IC17") (pin "7") (pinfunction "OE_7") (pintype "passive"))
      (node (ref "IC17") (pin "8") (pinfunction "GND_8") (pintype "passive"))
      (node (ref "IC18") (pin "7") (pinfunction "OE_7") (pintype "passive"))
      (node (ref "IC18") (pin "8") (pinfunction "GND_8") (pintype "passive"))
      (node (ref "IC19") (pin "5") (pinfunction "DIR3_5") (pintype "passive"))
      (node (ref "IC19") (pin "7") (pinfunction "OE_7") (pintype "passive"))
      (node (ref "IC19") (pin "8") (pinfunction "GND_8") (pintype "passive"))
      (node (ref "IC22") (pin "7") (pinfunction "OE_7") (pintype "passive"))
      (node (ref "IC22") (pin "8") (pinfunction "GND_8") (pintype "passive"))
      (node (ref "IC23") (pin "11") (pinfunction "A0_11") (pintype "input"))
      (node (ref "IC23") (pin "12") (pinfunction "A1_12") (pintype "input"))
      (node (ref "IC23") (pin "13") (pinfunction "A2_13") (pintype "input"))
      (node (ref "IC23") (pin "6") (pinfunction "VSS_6") (pintype "power_in"))
      (node (ref "IC23") (pin "PAD") (pinfunction "GND_PAD") (pintype "passive"))
      (node (ref "IC8") (pin "2") (pinfunction "GND_2") (pintype "passive"))
      (node (ref "R162") (pin "2") (pinfunction "2_2") (pintype "passive"))
      (node (ref "R163") (pin "2") (pinfunction "2_2") (pintype "passive"))
      (node (ref "R164") (pin "2") (pinfunction "2_2") (pintype "passive"))
      (node (ref "R165") (pin "2") (pinfunction "2_2") (pintype "passive"))
      (node (ref "R166") (pin "2") (pinfunction "2_2") (pintype "passive"))
      (node (ref "R167") (pin "2") (pinfunction "2_2") (pintype "passive"))
      (node (ref "R168") (pin "2") (pinfunction "2_2") (pintype "passive"))
      (node (ref "R169") (pin "2") (pinfunction "2_2") (pintype "passive"))
      (node (ref "R78") (pin "2") (pinfunction "2_2") (pintype "passive"))
      (node (ref "R88") (pin "1") (pinfunction "1_1") (pintype "passive"))
      (node (ref "R93") (pin "1") (pinfunction "1_1") (pintype "passive"))
      (node (ref "R96") (pin "1") (pinfunction "1_1") (pintype "passive"))
      (node (ref "X10") (pin "0") (pinfunction "GND_0") (pintype "passive"))
      (node (ref "X10") (pin "15") (pinfunction "GND_15") (pintype "passive"))
      (node (ref "X10") (pin "18") (pinfunction "GND_18") (pintype "passive"))
      (node (ref "X10") (pin "21") (pinfunction "GND_21") (pintype "passive"))
      (node (ref "X10") (pin "26") (pinfunction "GND_26") (pintype "passive"))
      (node (ref "X10") (pin "27") (pinfunction "GND_27") (pintype "passive"))
      (node (ref "X10") (pin "29") (pinfunction "GND_29") (pintype "passive"))
      (node (ref "X10") (pin "34") (pinfunction "GND_34") (pintype "passive"))
      (node (ref "X10") (pin "35") (pinfunction "GND_35") (pintype "passive"))
      (node (ref "X10") (pin "4") (pinfunction "GND_4") (pintype "passive"))
      (node (ref "X10") (pin "40") (pinfunction "GND_40") (pintype "passive"))
      (node (ref "X10") (pin "50") (pinfunction "GND_50") (pintype "passive"))
      (node (ref "X10") (pin "9") (pinfunction "GND_9") (pintype "passive"))
      (node (ref "X11") (pin "6") (pinfunction "6_6") (pintype "passive"))
      (node (ref "X5") (pin "2") (pinfunction "Y_2") (pintype "passive"))
    )
    (net (code "81") (name "Net-(C156-Pad1)") (class "Default")
      (node (ref "C156") (pin "1") (pinfunction "1_1") (pintype "passive"))
      (node (ref "L1") (pin "2") (pinfunction "2_2") (pintype "passive"))
      (node (ref "R153") (pin "1") (pinfunction "1_1") (pintype "passive"))
    )
    (net (code "82") (name "Net-(IC10-UART_RX)") (class "Default")
      (node (ref "FR36") (pin "2") (pinfunction "2_2") (pintype "passive"))
      (node (ref "IC10") (pin "9") (pinfunction "UART_RX_9") (pintype "input"))
    )
    (net (code "83") (name "Net-(IC10-UART_TX)") (class "Default")
      (node (ref "FR37") (pin "2") (pinfunction "2_2") (pintype "passive"))
      (node (ref "IC10") (pin "10") (pinfunction "UART_TX_10") (pintype "output"))
    )
    (net (code "84") (name "Net-(LED1-C)") (class "Default")
      (node (ref "LED1") (pin "K") (pinfunction "C_K") (pintype "power_in"))
      (node (ref "R97") (pin "1") (pinfunction "1_1") (pintype "passive"))
    )
    (net (code "85") (name "Net-(LED2-C)") (class "Default")
      (node (ref "LED2") (pin "K") (pinfunction "C_K") (pintype "power_in"))
      (node (ref "R102") (pin "1") (pinfunction "1_1") (pintype "passive"))
    )
    (net (code "86") (name "Net-(R93-Pad2)") (class "Default")
      (node (ref "R93") (pin "2") (pinfunction "2_2") (pintype "passive"))
      (node (ref "X10") (pin "37") (pinfunction "Reserved_37") (pintype "passive"))
    )
    (net (code "87") (name "Net-(R96-Pad2)") (class "Default")
      (node (ref "R96") (pin "2") (pinfunction "2_2") (pintype "passive"))
      (node (ref "X10") (pin "43") (pinfunction "Reserved_43") (pintype "passive"))
    )
    (net (code "88") (name "Net-(R98-Pad2)") (class "Default")
      (node (ref "R98") (pin "2") (pinfunction "2_2") (pintype "passive"))
      (node (ref "X10") (pin "45") (pinfunction "Reserved_45") (pintype "passive"))
    )
    (net (code "89") (name "Net-(R174-Pad1)") (class "Default")
      (node (ref "R174") (pin "1") (pinfunction "1_1") (pintype "passive"))
      (node (ref "VT1") (pin "G") (pinfunction "G_G") (pintype "passive"))
    )
    (net (code "90") (name "Net-(X10-Reserved(UIM_C4))") (class "Default")
      (node (ref "R86") (pin "2") (pinfunction "2_2") (pintype "passive"))
      (node (ref "X10") (pin "19") (pinfunction "Reserved(UIM_C4)_19") (pintype "passive"))
    )
    (net (code "91") (name "Net-(X10-SMB_CLK)") (class "Default")
      (node (ref "R176") (pin "1") (pinfunction "1_1") (pintype "passive"))
      (node (ref "R90") (pin "1") (pinfunction "1_1") (pintype "passive"))
      (node (ref "X10") (pin "30") (pinfunction "SMB_CLK_30") (pintype "passive"))
    )
    (net (code "92") (name "Net-(X10-SMB_DATA)") (class "Default")
      (node (ref "R91") (pin "1") (pinfunction "1_1") (pintype "passive"))
      (node (ref "X10") (pin "32") (pinfunction "SMB_DATA_32") (pintype "passive"))
    )
    (net (code "93") (name "VCC1P8") (class "Default")
      (node (ref "C224") (pin "2") (pinfunction "2_2") (pintype "passive"))
      (node (ref "C226") (pin "2") (pinfunction "2_2") (pintype "passive"))
      (node (ref "C228") (pin "2") (pinfunction "2_2") (pintype "passive"))
      (node (ref "C230") (pin "2") (pinfunction "2_2") (pintype "passive"))
      (node (ref "IC17") (pin "14") (pinfunction "VCCA_14") (pintype "passive"))
      (node (ref "IC17") (pin "15") (pinfunction "DIR1_15") (pintype "passive"))
      (node (ref "IC17") (pin "5") (pinfunction "DIR3_5") (pintype "passive"))
      (node (ref "IC18") (pin "14") (pinfunction "VCCA_14") (pintype "passive"))
      (node (ref "IC18") (pin "15") (pinfunction "DIR1_15") (pintype "passive"))
      (node (ref "IC18") (pin "16") (pinfunction "DIR2_16") (pintype "passive"))
      (node (ref "IC18") (pin "5") (pinfunction "DIR3_5") (pintype "passive"))
      (node (ref "IC18") (pin "6") (pinfunction "DIR4_6") (pintype "passive"))
      (node (ref "IC19") (pin "14") (pinfunction "VCCA_14") (pintype "passive"))
      (node (ref "IC19") (pin "15") (pinfunction "DIR1_15") (pintype "passive"))
      (node (ref "IC19") (pin "16") (pinfunction "DIR2_16") (pintype "passive"))
      (node (ref "IC19") (pin "6") (pinfunction "DIR4_6") (pintype "passive"))
      (node (ref "IC22") (pin "14") (pinfunction "VCCA_14") (pintype "passive"))
      (node (ref "IC22") (pin "15") (pinfunction "DIR1_15") (pintype "passive"))
      (node (ref "IC22") (pin "16") (pinfunction "DIR2_16") (pintype "passive"))
      (node (ref "IC22") (pin "5") (pinfunction "DIR3_5") (pintype "passive"))
      (node (ref "IC22") (pin "6") (pinfunction "DIR4_6") (pintype "passive"))
      (node (ref "R154") (pin "1") (pinfunction "1_1") (pintype "passive"))
      (node (ref "R155") (pin "1") (pinfunction "1_1") (pintype "passive"))
      (node (ref "R156") (pin "1") (pinfunction "1_1") (pintype "passive"))
      (node (ref "R157") (pin "1") (pinfunction "1_1") (pintype "passive"))
      (node (ref "R158") (pin "1") (pinfunction "1_1") (pintype "passive"))
      (node (ref "R159") (pin "1") (pinfunction "1_1") (pintype "passive"))
      (node (ref "R160") (pin "1") (pinfunction "1_1") (pintype "passive"))
      (node (ref "R161") (pin "1") (pinfunction "1_1") (pintype "passive"))
      (node (ref "R178") (pin "1") (pinfunction "1_1") (pintype "passive"))
      (node (ref "VT2") (pin "G") (pinfunction "G_G") (pintype "passive"))
    )
    (net (code "94") (name "VCC3P3") (class "Default")
      (node (ref "C160") (pin "1") (pinfunction "1_1") (pintype "passive"))
      (node (ref "C170") (pin "1") (pinfunction "1_1") (pintype "passive"))
      (node (ref "C225") (pin "1") (pinfunction "1_1") (pintype "passive"))
      (node (ref "C227") (pin "1") (pinfunction "1_1") (pintype "passive"))
      (node (ref "C229") (pin "1") (pinfunction "1_1") (pintype "passive"))
      (node (ref "C231") (pin "1") (pinfunction "1_1") (pintype "passive"))
      (node (ref "C233") (pin "1") (pinfunction "1_1") (pintype "passive"))
      (node (ref "IC13") (pin "8") (pinfunction "VCC_8") (pintype "power_in"))
      (node (ref "IC17") (pin "13") (pinfunction "VCCB_13") (pintype "passive"))
      (node (ref "IC18") (pin "13") (pinfunction "VCCB_13") (pintype "passive"))
      (node (ref "IC19") (pin "13") (pinfunction "VCCB_13") (pintype "passive"))
      (node (ref "IC22") (pin "13") (pinfunction "VCCB_13") (pintype "passive"))
      (node (ref "IC23") (pin "5") (pinfunction "VDD_5") (pintype "power_in"))
      (node (ref "IC8") (pin "5") (pinfunction "V+_5") (pintype "power_in"))
      (node (ref "LED1") (pin "A") (pinfunction "A_A") (pintype "power_in"))
      (node (ref "LED2") (pin "A") (pinfunction "A_A") (pintype "power_in"))
      (node (ref "R170") (pin "1") (pinfunction "1_1") (pintype "passive"))
      (node (ref "R175") (pin "1") (pinfunction "1_1") (pintype "passive"))
      (node (ref "R179") (pin "1") (pinfunction "1_1") (pintype "passive"))
      (node (ref "X11") (pin "1") (pinfunction "1_1") (pintype "passive"))
    )
    (net (code "95") (name "VCC3P3_CLK") (class "Default")
      (node (ref "FR38") (pin "1") (pinfunction "1_1") (pintype "passive"))
    )
    (net (code "96") (name "VCC3P3_GNSS") (class "Default")
      (node (ref "C166") (pin "2") (pinfunction "2_2") (pintype "passive"))
      (node (ref "C167") (pin "2") (pinfunction "2_2") (pintype "passive"))
      (node (ref "FR38") (pin "2") (pinfunction "2_2") (pintype "passive"))
      (node (ref "IC10") (pin "14") (pinfunction "BV_14") (pintype "power_in"))
      (node (ref "IC10") (pin "15") (pinfunction "VCC_15") (pintype "power_in"))
      (node (ref "R153") (pin "2") (pinfunction "2_2") (pintype "passive"))
    )
    (net (code "97") (name "VCC3P3_MPCIE") (class "Default")
      (node (ref "R180") (pin "2") (pinfunction "2_2") (pintype "passive"))
      (node (ref "X10") (pin "2") (pinfunction "+3.3V_2") (pintype "passive"))
      (node (ref "X10") (pin "52") (pinfunction "+3.3V_52") (pintype "passive"))
    )
    (net (code "98") (name "unconnected-(IC8-ALERT-Pad3)") (class "Default")
      (node (ref "IC8") (pin "3") (pinfunction "ALERT_3") (pintype "output+no_connect"))
    )
    (net (code "99") (name "unconnected-(IC10-E2-Pad11)") (class "Default")
      (node (ref "IC10") (pin "11") (pinfunction "E2_11") (pintype "passive+no_connect"))
    )
    (net (code "100") (name "unconnected-(IC10-E3-Pad12)") (class "Default")
      (node (ref "IC10") (pin "12") (pinfunction "E3_12") (pintype "passive+no_connect"))
    )
    (net (code "101") (name "unconnected-(IC18-A3-Pad3)") (class "Default")
      (node (ref "IC18") (pin "3") (pinfunction "A3_3") (pintype "passive"))
    )
    (net (code "102") (name "unconnected-(IC18-A4-Pad4)") (class "Default")
      (node (ref "IC18") (pin "4") (pinfunction "A4_4") (pintype "passive"))
    )
    (net (code "103") (name "unconnected-(IC18-B3-Pad10)") (class "Default")
      (node (ref "IC18") (pin "10") (pinfunction "B3_10") (pintype "passive"))
    )
    (net (code "104") (name "unconnected-(IC18-B4-Pad9)") (class "Default")
      (node (ref "IC18") (pin "9") (pinfunction "B4_9") (pintype "passive"))
    )
    (net (code "105") (name "unconnected-(IC23-INTA-Pad16)") (class "Default")
      (node (ref "IC23") (pin "16") (pinfunction "INTA_16") (pintype "open_collector+no_connect"))
    )
    (net (code "106") (name "unconnected-(IC23-INTB-Pad15)") (class "Default")
      (node (ref "IC23") (pin "15") (pinfunction "INTB_15") (pintype "open_collector+no_connect"))
    )
    (net (code "107") (name "unconnected-(IC23-NC-Pad7)") (class "Default")
      (node (ref "IC23") (pin "7") (pinfunction "NC_7") (pintype "passive+no_connect"))
    )
    (net (code "108") (name "unconnected-(IC23-NC-Pad10)") (class "Default")
      (node (ref "IC23") (pin "10") (pinfunction "NC_10") (pintype "passive+no_connect"))
    )
    (net (code "109") (name "unconnected-(X10-+1.5V-Pad6)") (class "Default")
      (node (ref "X10") (pin "6") (pinfunction "+1.5V_6") (pintype "passive+no_connect"))
    )
    (net (code "110") (name "unconnected-(X10-+1.5V-Pad28)") (class "Default")
      (node (ref "X10") (pin "28") (pinfunction "+1.5V_28") (pintype "passive+no_connect"))
    )
    (net (code "111") (name "unconnected-(X10-+1.5V-Pad48)") (class "Default")
      (node (ref "X10") (pin "48") (pinfunction "+1.5V_48") (pintype "passive+no_connect"))
    )
    (net (code "112") (name "unconnected-(X10-+3.3Vaux-Pad24)") (class "Default")
      (node (ref "X10") (pin "24") (pinfunction "+3.3Vaux_24") (pintype "passive+no_connect"))
    )
    (net (code "113") (name "unconnected-(X10-UIM_CLK-Pad12)") (class "Default")
      (node (ref "X10") (pin "12") (pinfunction "UIM_CLK_12") (pintype "passive+no_connect"))
    )
    (net (code "114") (name "unconnected-(X10-UIM_DATA-Pad10)") (class "Default")
      (node (ref "X10") (pin "10") (pinfunction "UIM_DATA_10") (pintype "passive+no_connect"))
    )
    (net (code "115") (name "unconnected-(X10-UIM_PWR-Pad8)") (class "Default")
      (node (ref "X10") (pin "8") (pinfunction "UIM_PWR_8") (pintype "passive+no_connect"))
    )
    (net (code "116") (name "unconnected-(X10-UIM_RESET-Pad14)") (class "Default")
      (node (ref "X10") (pin "14") (pinfunction "UIM_RESET_14") (pintype "passive+no_connect"))
    )
    (net (code "117") (name "unconnected-(X10-UIM_VPP-Pad16)") (class "Default")
      (node (ref "X10") (pin "16") (pinfunction "UIM_VPP_16") (pintype "passive+no_connect"))
    )
    (net (code "118") (name "unconnected-(X10-USB_DM-Pad36)") (class "Default")
      (node (ref "X10") (pin "36") (pinfunction "USB_DM_36") (pintype "passive+no_connect"))
    )
    (net (code "119") (name "unconnected-(X10-USB_DP-Pad38)") (class "Default")
      (node (ref "X10") (pin "38") (pinfunction "USB_DP_38") (pintype "passive+no_connect"))
    )
    (net (code "120") (name "unconnected-(X10-WAKE#-Pad1)") (class "Default")
      (node (ref "X10") (pin "1") (pinfunction "WAKE#_1") (pintype "passive+no_connect"))
    )
    (net (code "121") (name "unconnected-(X11-Pad3)") (class "Default")
      (node (ref "X11") (pin "3") (pinfunction "3_3") (pintype "passive"))
    )
    (net (code "122") (name "unconnected-(X11-Pad4)") (class "Default")
      (node (ref "X11") (pin "4") (pinfunction "4_4") (pintype "passive"))
    )
  )
)
